# CarrierBoard.net
KiCad netlist of a schematic drawn in Altium Designer
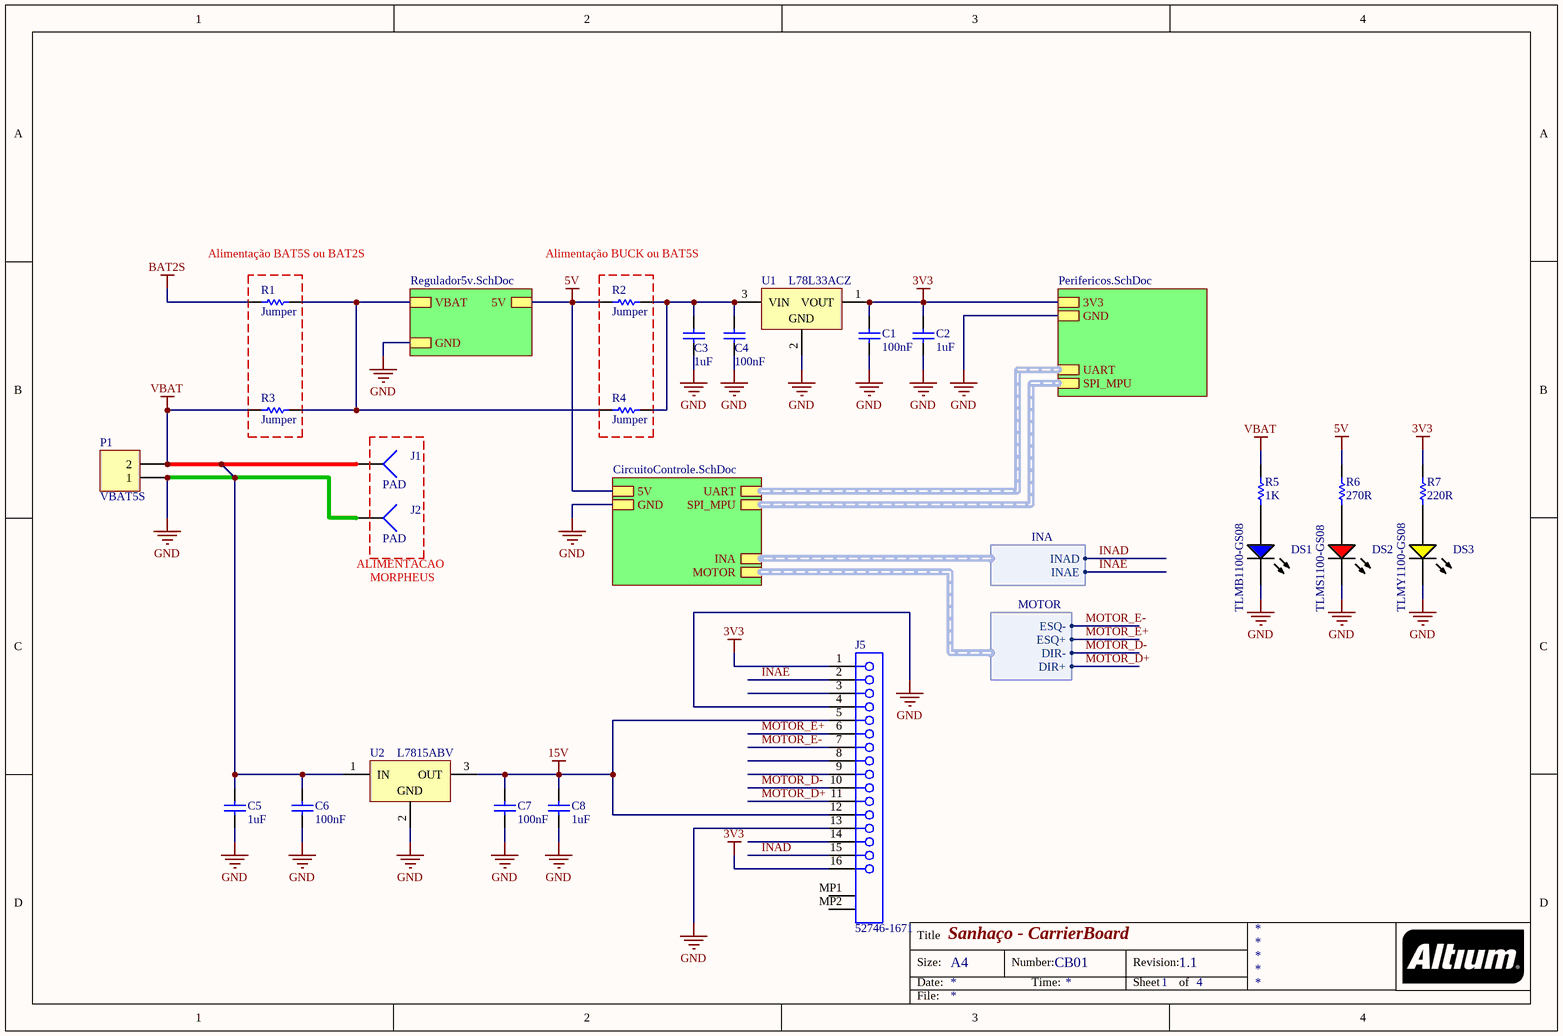
[diagram p0: CarrierBoard.SchDoc]

(export (version "E")
  (design (tool "Eeschema 10.0.6"))
  (components
    (comp (ref "C1")
      (value "100nF")
      (footprint "CAPC0805(2012)145_N")
      (description "CAP 100nF 50V ±5% 0805 (2012 Metric) Thickness 1.45mm SMD")
      (fields (field (name "TOLERANCE") "Â±5%"))
      (libsource (lib "Altium Content Vault") (part "CAP"))
    )
    (comp (ref "C2")
      (value "1uF")
      (footprint "CAPC0805(2012)145_L")
      (description "CAP 1uF 50V ±10% 0805 (2012 Metric) Thickness 1.45mm SMD")
      (fields (field (name "TOLERANCE") "Â±10%"))
      (libsource (lib "Altium Content Vault") (part "CAP"))
    )
    (comp (ref "C3")
      (value "1uF")
      (footprint "CAPC0805(2012)145_L")
      (description "CAP 1uF 50V ±10% 0805 (2012 Metric) Thickness 1.45mm SMD")
      (fields (field (name "TOLERANCE") "Â±10%"))
      (libsource (lib "Altium Content Vault") (part "CAP"))
    )
    (comp (ref "C4")
      (value "100nF")
      (footprint "CAPC0805(2012)145_N")
      (description "CAP 100nF 50V ±5% 0805 (2012 Metric) Thickness 1.45mm SMD")
      (fields (field (name "TOLERANCE") "Â±5%"))
      (libsource (lib "Altium Content Vault") (part "CAP"))
    )
    (comp (ref "C5")
      (value "1uF")
      (footprint "CAPC0805(2012)145_L")
      (description "CAP 1uF 50V ±10% 0805 (2012 Metric) Thickness 1.45mm SMD")
      (fields (field (name "TOLERANCE") "Â±10%"))
      (libsource (lib "Altium Content Vault") (part "CAP"))
    )
    (comp (ref "C6")
      (value "100nF")
      (footprint "CAPC0805(2012)145_N")
      (description "CAP 100nF 50V ±5% 0805 (2012 Metric) Thickness 1.45mm SMD")
      (fields (field (name "TOLERANCE") "Â±5%"))
      (libsource (lib "Altium Content Vault") (part "CAP"))
    )
    (comp (ref "C7")
      (value "100nF")
      (footprint "CAPC0805(2012)145_N")
      (description "CAP 100nF 50V ±5% 0805 (2012 Metric) Thickness 1.45mm SMD")
      (fields (field (name "TOLERANCE") "Â±5%"))
      (libsource (lib "Altium Content Vault") (part "CAP"))
    )
    (comp (ref "C8")
      (value "1uF")
      (footprint "CAPC0805(2012)145_L")
      (description "CAP 1uF 50V ±10% 0805 (2012 Metric) Thickness 1.45mm SMD")
      (fields (field (name "TOLERANCE") "Â±10%"))
      (libsource (lib "Altium Content Vault") (part "CAP"))
    )
    (comp (ref "DS1")
      (value "TLMB1100-GS08")
      (footprint "VISH-TLMX1100-2_V")
      (fields (field (name "TOLERANCE") "10%"))
      (libsource (lib "TLMB110-GS08") (part "CMP-1666-00028-1"))
    )
    (comp (ref "DS2")
      (value "TLMS1100-GS08")
      (footprint "VISH-TLMX1100_V")
      (description "LED, RED, 2.1 V, -40 to 100 degC, 2-Pin SMD (0603), RoHS, Tape and Reel")
      (fields (field (name "TOLERANCE") "5%"))
      (libsource (lib "TLMS1100-GS08(RED)") (part "CMP-1666-00027-1"))
    )
    (comp (ref "DS3")
      (value "TLMY1100-GS08")
      (footprint "VISH-TLMX1100-2_V")
      (libsource (lib "TLMY1100-GS08(YELLOW)") (part "CMP-1666-00030-1"))
    )
    (comp (ref "J1")
      (value "PAD")
      (footprint "PIN1")
      (description "Socket")
      (fields (field (name "PUBLISHER") "Altium Limited"))
      (libsource (lib "Miscellaneous Connectors") (part "Socket"))
    )
    (comp (ref "J2")
      (value "PAD")
      (footprint "PIN1")
      (description "Socket")
      (fields (field (name "PUBLISHER") "Altium Limited"))
      (libsource (lib "Miscellaneous Connectors") (part "Socket"))
    )
    (comp (ref "J5")
      (value "52746-1671")
      (footprint "MOLX-52746-1671")
      (fields (field (name "MANUFACTURER") "Molex"))
      (libsource (lib "52746-1671.5mm16") (part "CMP-1241-00378-1"))
    )
    (comp (ref "P1")
      (value "VBAT5S")
      (footprint "HDR1X2")
      (description "Header, 2-Pin")
      (fields (field (name "PUBLISHER") "Altium Limited"))
      (libsource (lib "Miscellaneous Connectors") (part "Header 2"))
    )
    (comp (ref "R1")
      (value "Jumper")
      (footprint "RESC0805(2012)_N")
      (description "Jumper 0805 (2012 Metric)")
      (fields (field (name "TOLERANCE") "None"))
      (libsource (lib "Altium Content Vault") (part "RES"))
    )
    (comp (ref "R2")
      (value "Jumper")
      (footprint "RESC0805(2012)_N")
      (description "Jumper 0805 (2012 Metric)")
      (fields (field (name "TOLERANCE") "None"))
      (libsource (lib "Altium Content Vault") (part "RES"))
    )
    (comp (ref "R3")
      (value "Jumper")
      (footprint "RESC0805(2012)_N")
      (description "Jumper 0805 (2012 Metric)")
      (fields (field (name "TOLERANCE") "None"))
      (libsource (lib "Altium Content Vault") (part "RES"))
    )
    (comp (ref "R4")
      (value "Jumper")
      (footprint "RESC0805(2012)_N")
      (description "Jumper 0805 (2012 Metric)")
      (fields (field (name "TOLERANCE") "None"))
      (libsource (lib "Altium Content Vault") (part "RES"))
    )
    (comp (ref "R5")
      (value "1K")
      (footprint "RESC0805(2012)_N")
      (description "1K 0.125W 5% 0805 (2012 Metric)  SMD                                667-ERJ-P06J102V")
      (fields (field (name "POWER") "0.500 W") (field (name "TOLERANCE") "5 %"))
      (libsource (lib "Resistor 0805 1k") (part "CMP-1013-00074-1"))
    )
    (comp (ref "R6")
      (value "270R")
      (footprint "RESC0402(1005)_N")
      (description "270R 0.063W 5% 0402 (1005 Metric)  SMD                             603-AC0402JR-07270RL")
      (fields (field (name "TOLERANCE") "5 %") (field (name "POWER") "0.063 W"))
      (libsource (lib "Altium Content Vault") (part "RES"))
    )
    (comp (ref "R7")
      (value "220R")
      (footprint "RESC0805(2012)_N")
      (description "220R 0.125W 5% 0805 (2012 Metric)  SMD                               603-RC0805JR-7W220RL")
      (fields (field (name "POWER") "0.250 W") (field (name "TOLERANCE") "5 %"))
      (libsource (lib "Resistor 2012 220R") (part "CMP-1013-00058-1"))
    )
    (comp (ref "U1")
      (value "L78L33ACZ")
      (footprint "TO-92")
      (description "Positive Voltage Regulator, 3.3V, 3-Pin TO-92")
      (libsource (lib "Altium Content Vault") (part "PM-REG-7805-SIL3"))
    )
    (comp (ref "U2")
      (value "L7815ABV")
      (footprint "TO220")
      (description "Positive Voltage Regulator, 15V, 3-Pin TO-220")
      (libsource (lib "Altium Content Vault") (part "PM-REG-L4940-SIL3"))
    )
  )
  (nets
    (net (code "3") (name "/INAD") (class "Default")
      (node (ref "J5") (pin "15") (pinfunction "15_15") (pintype "passive"))
    )
    (net (code "4") (name "/INAE") (class "Default")
      (node (ref "J5") (pin "2") (pinfunction "2_2") (pintype "passive"))
    )
    (net (code "5") (name "/MOTOR_D+") (class "Default")
      (node (ref "J5") (pin "11") (pinfunction "11_11") (pintype "passive"))
    )
    (net (code "6") (name "/MOTOR_D-") (class "Default")
      (node (ref "J5") (pin "10") (pinfunction "10_10") (pintype "passive"))
    )
    (net (code "7") (name "/MOTOR_E+") (class "Default")
      (node (ref "J5") (pin "6") (pinfunction "6_6") (pintype "passive"))
    )
    (net (code "8") (name "/MOTOR_E-") (class "Default")
      (node (ref "J5") (pin "7") (pinfunction "7_7") (pintype "passive"))
    )
    (net (code "11") (name "/VBAT") (class "Default")
      (node (ref "R1") (pin "2") (pinfunction "2_2") (pintype "passive"))
      (node (ref "R3") (pin "2") (pinfunction "2_2") (pintype "passive"))
      (node (ref "R4") (pin "1") (pinfunction "1_1") (pintype "passive"))
    )
    (net (code "14") (name "3V3") (class "Default")
      (node (ref "C1") (pin "2") (pinfunction "2_2") (pintype "passive"))
      (node (ref "C2") (pin "2") (pinfunction "2_2") (pintype "passive"))
      (node (ref "J5") (pin "1") (pinfunction "1_1") (pintype "passive"))
      (node (ref "J5") (pin "16") (pinfunction "16_16") (pintype "passive"))
      (node (ref "R7") (pin "2") (pinfunction "2_2") (pintype "passive"))
      (node (ref "U1") (pin "1") (pinfunction "VOUT_1") (pintype "power_in"))
    )
    (net (code "15") (name "5V") (class "Default")
      (node (ref "R2") (pin "1") (pinfunction "1_1") (pintype "passive"))
      (node (ref "R6") (pin "2") (pinfunction "2_2") (pintype "passive"))
    )
    (net (code "16") (name "15V") (class "Default")
      (node (ref "C7") (pin "2") (pinfunction "2_2") (pintype "passive"))
      (node (ref "C8") (pin "2") (pinfunction "2_2") (pintype "passive"))
      (node (ref "J5") (pin "12") (pinfunction "12_12") (pintype "passive"))
      (node (ref "J5") (pin "5") (pinfunction "5_5") (pintype "passive"))
      (node (ref "U2") (pin "3") (pinfunction "OUT_3") (pintype "power_in"))
    )
    (net (code "17") (name "BAT2S") (class "Default")
      (node (ref "R1") (pin "1") (pinfunction "1_1") (pintype "passive"))
    )
    (net (code "18") (name "GND") (class "Default")
      (node (ref "C1") (pin "1") (pinfunction "1_1") (pintype "passive"))
      (node (ref "C2") (pin "1") (pinfunction "1_1") (pintype "passive"))
      (node (ref "C3") (pin "1") (pinfunction "1_1") (pintype "passive"))
      (node (ref "C4") (pin "1") (pinfunction "1_1") (pintype "passive"))
      (node (ref "C5") (pin "1") (pinfunction "1_1") (pintype "passive"))
      (node (ref "C5") (pin "2") (pinfunction "2_2") (pintype "passive"))
      (node (ref "C6") (pin "1") (pinfunction "1_1") (pintype "passive"))
      (node (ref "C6") (pin "2") (pinfunction "2_2") (pintype "passive"))
      (node (ref "C7") (pin "1") (pinfunction "1_1") (pintype "passive"))
      (node (ref "C8") (pin "1") (pinfunction "1_1") (pintype "passive"))
      (node (ref "DS1") (pin "2") (pinfunction "K_2") (pintype "passive"))
      (node (ref "DS2") (pin "2") (pinfunction "K_2") (pintype "passive"))
      (node (ref "DS3") (pin "2") (pinfunction "K_2") (pintype "passive"))
      (node (ref "J1") (pin "1") (pinfunction "1_1") (pintype "passive"))
      (node (ref "J2") (pin "1") (pinfunction "1_1") (pintype "passive"))
      (node (ref "J5") (pin "13") (pinfunction "13_13") (pintype "passive"))
      (node (ref "J5") (pin "4") (pinfunction "4_4") (pintype "passive"))
      (node (ref "P1") (pin "1") (pinfunction "1_1") (pintype "passive"))
      (node (ref "P1") (pin "2") (pinfunction "2_2") (pintype "passive"))
      (node (ref "R3") (pin "1") (pinfunction "1_1") (pintype "passive"))
      (node (ref "R5") (pin "2") (pinfunction "2_2") (pintype "passive"))
      (node (ref "U1") (pin "2") (pinfunction "GND_2") (pintype "power_in"))
      (node (ref "U2") (pin "1") (pinfunction "IN_1") (pintype "power_in"))
      (node (ref "U2") (pin "2") (pinfunction "GND_2") (pintype "power_in"))
    )
    (net (code "19") (name "Net-(DS1-A)") (class "Default")
      (node (ref "DS1") (pin "1") (pinfunction "A_1") (pintype "passive"))
      (node (ref "R5") (pin "1") (pinfunction "1_1") (pintype "passive"))
    )
    (net (code "20") (name "Net-(DS2-A)") (class "Default")
      (node (ref "DS2") (pin "1") (pinfunction "A_1") (pintype "passive"))
      (node (ref "R6") (pin "1") (pinfunction "1_1") (pintype "passive"))
    )
    (net (code "21") (name "Net-(DS3-A)") (class "Default")
      (node (ref "DS3") (pin "1") (pinfunction "A_1") (pintype "passive"))
      (node (ref "R7") (pin "1") (pinfunction "1_1") (pintype "passive"))
    )
    (net (code "22") (name "Net-(U1-VIN)") (class "Default")
      (node (ref "C3") (pin "2") (pinfunction "2_2") (pintype "passive"))
      (node (ref "C4") (pin "2") (pinfunction "2_2") (pintype "passive"))
      (node (ref "R2") (pin "2") (pinfunction "2_2") (pintype "passive"))
      (node (ref "R4") (pin "2") (pinfunction "2_2") (pintype "passive"))
      (node (ref "U1") (pin "3") (pinfunction "VIN_3") (pintype "power_in"))
    )
    (net (code "23") (name "unconnected-(J5-Pad3)") (class "Default")
      (node (ref "J5") (pin "3") (pinfunction "3_3") (pintype "passive"))
    )
    (net (code "24") (name "unconnected-(J5-Pad8)") (class "Default")
      (node (ref "J5") (pin "8") (pinfunction "8_8") (pintype "passive"))
    )
    (net (code "25") (name "unconnected-(J5-Pad9)") (class "Default")
      (node (ref "J5") (pin "9") (pinfunction "9_9") (pintype "passive"))
    )
    (net (code "26") (name "unconnected-(J5-Pad14)") (class "Default")
      (node (ref "J5") (pin "14") (pinfunction "14_14") (pintype "passive"))
    )
    (net (code "27") (name "unconnected-(J5-PadMP1)") (class "Default")
      (node (ref "J5") (pin "MP1") (pinfunction "MP1_MP1") (pintype "passive"))
    )
    (net (code "28") (name "unconnected-(J5-PadMP2)") (class "Default")
      (node (ref "J5") (pin "MP2") (pinfunction "MP2_MP2") (pintype "passive"))
    )
  )
)
